# Schatten7.net
KiCad netlist of a schematic drawn in EAGLE
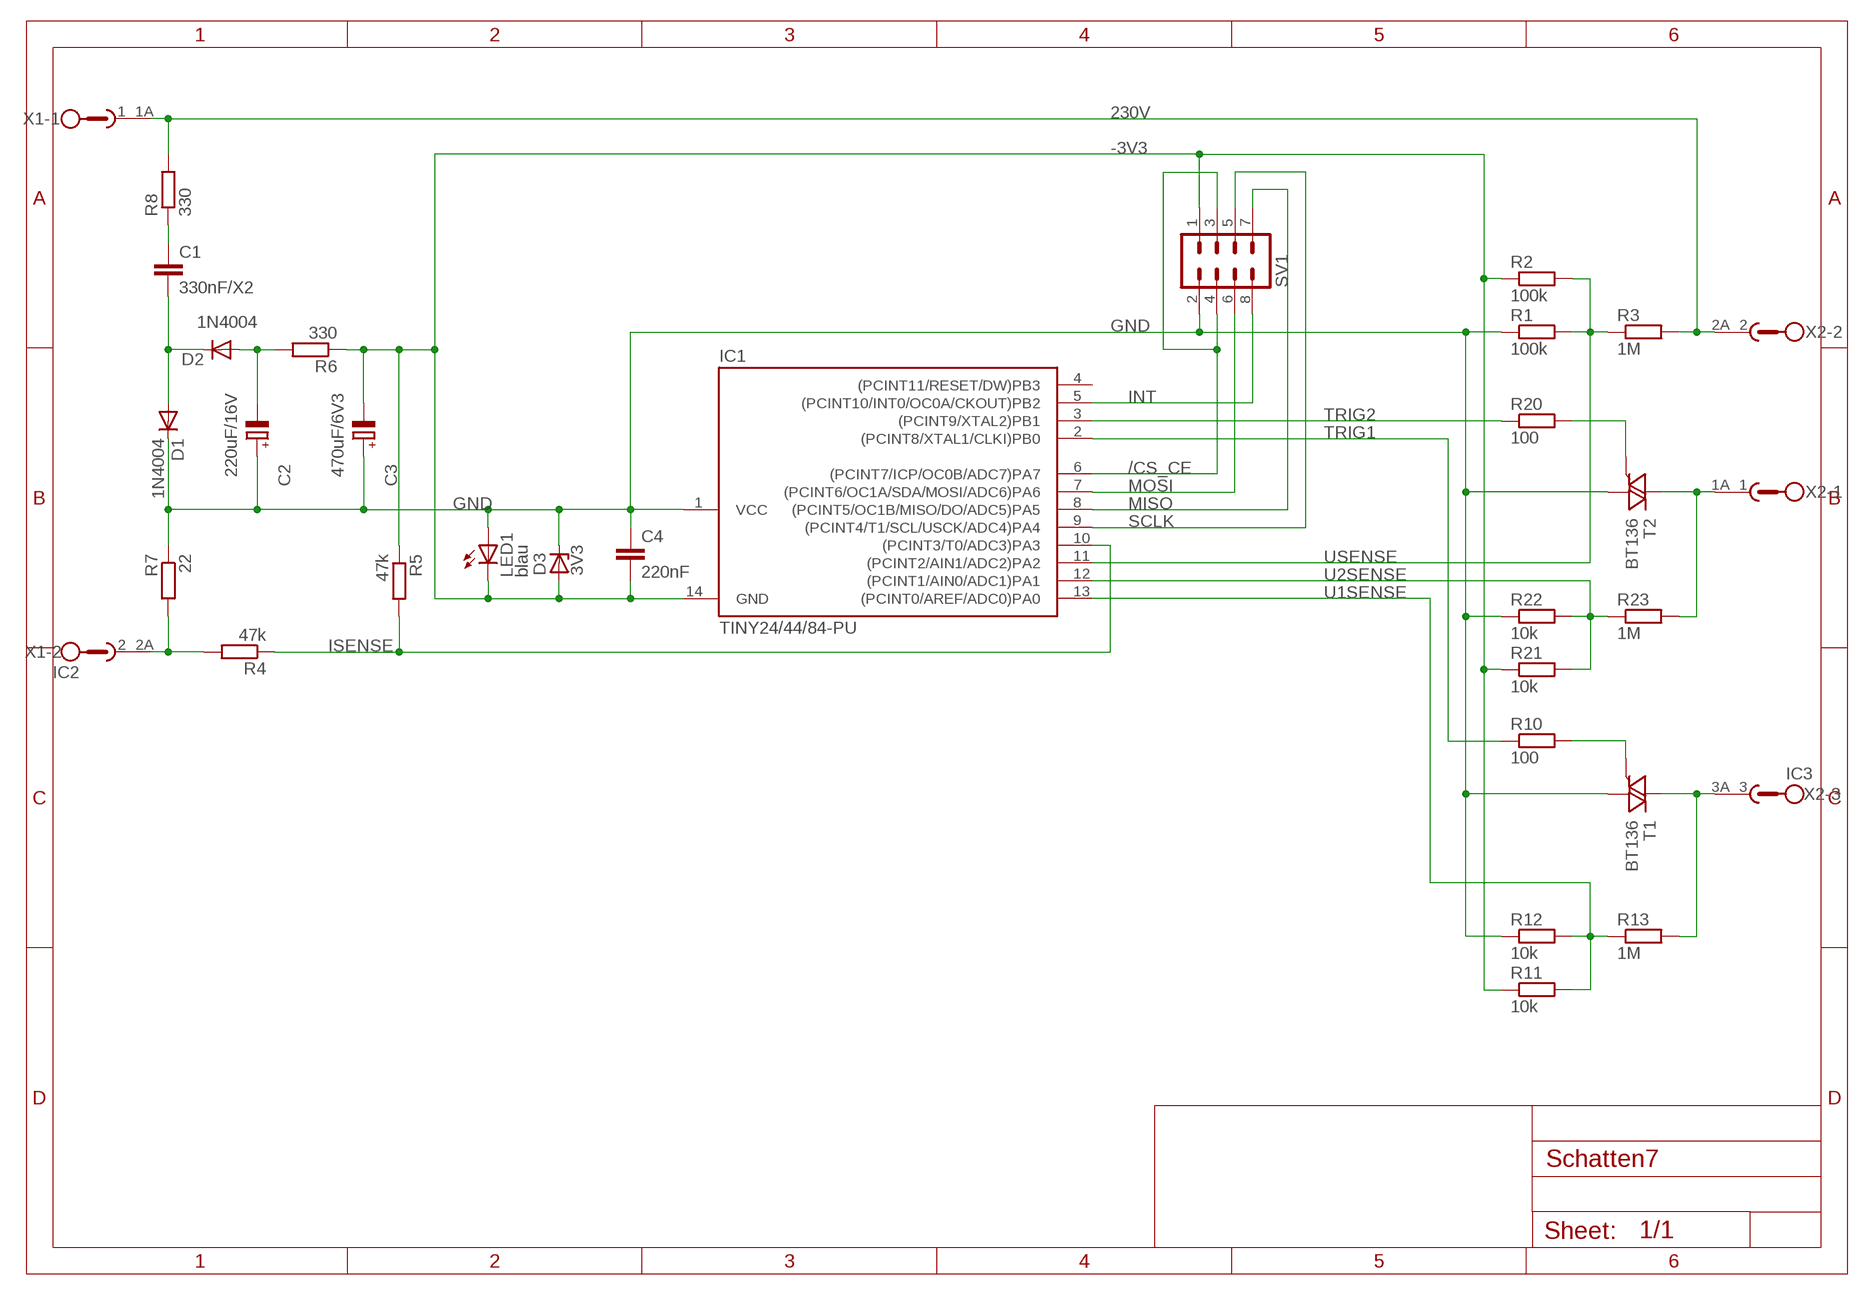
[diagram p0: schematic, sheet 1]

(export (version "E")
  (design (tool "Eeschema 10.0.6"))
  (components
    (comp (ref "C1")
      (value "330nF/X2")
      (footprint "eagle-import:C150-064X183")
      (libsource (lib "eagle-import") (part "C-EU150-064X183"))
    )
    (comp (ref "C2")
      (value "220uF/16V")
      (footprint "eagle-import:E5-8,5")
      (libsource (lib "eagle-import") (part "CPOL-EUE5-8.5"))
    )
    (comp (ref "C3")
      (value "470uF/6V3")
      (footprint "eagle-import:E5-8,5")
      (libsource (lib "eagle-import") (part "CPOL-EUE5-8.5"))
    )
    (comp (ref "C4")
      (value "220nF")
      (footprint "eagle-import:C3225")
      (libsource (lib "eagle-import") (part "C-EUC3225"))
    )
    (comp (ref "D1")
      (value "1N4004")
      (footprint "eagle-import:DO41-10")
      (libsource (lib "eagle-import") (part "1N4004"))
    )
    (comp (ref "D2")
      (value "1N4004")
      (footprint "eagle-import:DO41-10")
      (libsource (lib "eagle-import") (part "1N4004"))
    )
    (comp (ref "D3")
      (value "3V3")
      (footprint "eagle-import:ZDIO-7.5")
      (libsource (lib "eagle-import") (part "ZENER-DIODEZD-7.5"))
    )
    (comp (ref "IC1")
      (value "TINY24/44/84-PU")
      (footprint "eagle-import:DIL14")
      (libsource (lib "eagle-import") (part "TINY24/44/84-PU"))
    )
    (comp (ref "LED1")
      (value "blau")
      (footprint "eagle-import:LED3MM")
      (libsource (lib "eagle-import") (part "LED3MM"))
    )
    (comp (ref "R1")
      (value "100k")
      (footprint "eagle-import:0207_10")
      (libsource (lib "eagle-import") (part "R-EU_0207/10"))
    )
    (comp (ref "R2")
      (value "100k")
      (footprint "eagle-import:0207_10")
      (libsource (lib "eagle-import") (part "R-EU_0207/10"))
    )
    (comp (ref "R3")
      (value "1M")
      (footprint "eagle-import:0207_10")
      (libsource (lib "eagle-import") (part "R-EU_0207/10"))
    )
    (comp (ref "R4")
      (value "47k")
      (footprint "eagle-import:0207_10")
      (libsource (lib "eagle-import") (part "R-EU_0207/10"))
    )
    (comp (ref "R5")
      (value "47k")
      (footprint "eagle-import:0204V")
      (libsource (lib "eagle-import") (part "R-EU_0204/2V"))
    )
    (comp (ref "R6")
      (value "330")
      (footprint "eagle-import:0207_10")
      (libsource (lib "eagle-import") (part "R-EU_0207/10"))
    )
    (comp (ref "R7")
      (value "22")
      (footprint "eagle-import:0207_10")
      (libsource (lib "eagle-import") (part "R-EU_0207/10"))
    )
    (comp (ref "R8")
      (value "330")
      (footprint "eagle-import:0207_10")
      (libsource (lib "eagle-import") (part "R-EU_0207/10"))
    )
    (comp (ref "R10")
      (value "100")
      (footprint "eagle-import:0207_10")
      (libsource (lib "eagle-import") (part "R-EU_0207/10"))
    )
    (comp (ref "R11")
      (value "10k")
      (footprint "eagle-import:0204_7")
      (libsource (lib "eagle-import") (part "R-EU_0204/7"))
    )
    (comp (ref "R12")
      (value "10k")
      (footprint "eagle-import:0207_10")
      (libsource (lib "eagle-import") (part "R-EU_0207/10"))
    )
    (comp (ref "R13")
      (value "1M")
      (footprint "eagle-import:0207_10")
      (libsource (lib "eagle-import") (part "R-EU_0207/10"))
    )
    (comp (ref "R20")
      (value "100")
      (footprint "eagle-import:0207_10")
      (libsource (lib "eagle-import") (part "R-EU_0207/10"))
    )
    (comp (ref "R21")
      (value "10k")
      (footprint "eagle-import:0207_10")
      (libsource (lib "eagle-import") (part "R-EU_0207/10"))
    )
    (comp (ref "R22")
      (value "10k")
      (footprint "eagle-import:0207_10")
      (libsource (lib "eagle-import") (part "R-EU_0207/10"))
    )
    (comp (ref "R23")
      (value "1M")
      (footprint "eagle-import:0207_10")
      (libsource (lib "eagle-import") (part "R-EU_0207/10"))
    )
    (comp (ref "SV1")
      (value "MA04-2")
      (footprint "eagle-import:MA04-2")
      (libsource (lib "eagle-import") (part "MA04-2"))
    )
    (comp (ref "T1")
      (value "BT136")
      (footprint "eagle-import:TO220AB")
      (libsource (lib "eagle-import") (part "BT136"))
    )
    (comp (ref "T2")
      (value "BT136")
      (footprint "eagle-import:TO220AB")
      (libsource (lib "eagle-import") (part "BT136"))
    )
    (comp (ref "X1")
      (value "IC2")
      (footprint "eagle-import:IC2")
      (libsource (lib "eagle-import") (part "IC2"))
    )
    (comp (ref "X2")
      (value "IC3")
      (footprint "eagle-import:IC3")
      (libsource (lib "eagle-import") (part "IC3"))
    )
  )
  (nets
    (net (code "1") (name "/-3V3") (class "Default")
      (node (ref "C3") (pin "-") (pinfunction "-_-") (pintype "passive"))
      (node (ref "C4") (pin "2") (pinfunction "2_2") (pintype "passive"))
      (node (ref "D3") (pin "A") (pinfunction "A_A") (pintype "passive"))
      (node (ref "IC1") (pin "14") (pinfunction "GND_14") (pintype "power_in"))
      (node (ref "LED1") (pin "K") (pinfunction "C_K") (pintype "passive"))
      (node (ref "R11") (pin "1") (pinfunction "1_1") (pintype "passive"))
      (node (ref "R2") (pin "1") (pinfunction "1_1") (pintype "passive"))
      (node (ref "R21") (pin "1") (pinfunction "1_1") (pintype "passive"))
      (node (ref "R5") (pin "1") (pinfunction "1_1") (pintype "passive"))
      (node (ref "R6") (pin "1") (pinfunction "1_1") (pintype "passive"))
      (node (ref "SV1") (pin "1") (pinfunction "1_1") (pintype "passive"))
    )
    (net (code "2") (name "/230V") (class "Default")
      (node (ref "R3") (pin "2") (pinfunction "2_2") (pintype "passive"))
      (node (ref "R8") (pin "2") (pinfunction "2_2") (pintype "passive"))
      (node (ref "X1") (pin "1A") (pinfunction "2_1A") (pintype "passive"))
      (node (ref "X2") (pin "2A") (pinfunction "2_2A") (pintype "passive"))
    )
    (net (code "3") (name "/GND") (class "Default")
      (node (ref "C2") (pin "+") (pinfunction "+_+") (pintype "passive"))
      (node (ref "C3") (pin "+") (pinfunction "+_+") (pintype "passive"))
      (node (ref "C4") (pin "1") (pinfunction "1_1") (pintype "passive"))
      (node (ref "D1") (pin "C") (pinfunction "C_C") (pintype "passive"))
      (node (ref "D3") (pin "C") (pinfunction "C_C") (pintype "passive"))
      (node (ref "IC1") (pin "1") (pinfunction "VCC_1") (pintype "power_in"))
      (node (ref "LED1") (pin "A") (pinfunction "A_A") (pintype "passive"))
      (node (ref "R1") (pin "1") (pinfunction "1_1") (pintype "passive"))
      (node (ref "R12") (pin "1") (pinfunction "1_1") (pintype "passive"))
      (node (ref "R22") (pin "1") (pinfunction "1_1") (pintype "passive"))
      (node (ref "R7") (pin "1") (pinfunction "1_1") (pintype "passive"))
      (node (ref "SV1") (pin "2") (pinfunction "2_2") (pintype "passive"))
      (node (ref "T1") (pin "1") (pinfunction "A1_1") (pintype "passive"))
      (node (ref "T2") (pin "1") (pinfunction "A1_1") (pintype "passive"))
    )
    (net (code "4") (name "/INT") (class "Default")
      (node (ref "IC1") (pin "5") (pinfunction "(PCINT10/INT0/OC0A/CKOUT)PB2_5") (pintype "bidirectional"))
      (node (ref "SV1") (pin "8") (pinfunction "8_8") (pintype "passive"))
    )
    (net (code "5") (name "/ISENSE") (class "Default")
      (node (ref "IC1") (pin "10") (pinfunction "(PCINT3/T0/ADC3)PA3_10") (pintype "bidirectional"))
      (node (ref "R4") (pin "1") (pinfunction "1_1") (pintype "passive"))
      (node (ref "R5") (pin "2") (pinfunction "2_2") (pintype "passive"))
    )
    (net (code "6") (name "/MISO") (class "Default")
      (node (ref "IC1") (pin "8") (pinfunction "(PCINT5/OC1B/MISO/DO/ADC5)PA5_8") (pintype "bidirectional"))
      (node (ref "SV1") (pin "7") (pinfunction "7_7") (pintype "passive"))
    )
    (net (code "7") (name "/MOSI") (class "Default")
      (node (ref "IC1") (pin "7") (pinfunction "(PCINT6/OC1A/SDA/MOSI/ADC6)PA6_7") (pintype "bidirectional"))
      (node (ref "SV1") (pin "6") (pinfunction "6_6") (pintype "passive"))
    )
    (net (code "8") (name "/SCLK") (class "Default")
      (node (ref "IC1") (pin "9") (pinfunction "(PCINT4/T1/SCL/USCK/ADC4)PA4_9") (pintype "bidirectional"))
      (node (ref "SV1") (pin "5") (pinfunction "5_5") (pintype "passive"))
    )
    (net (code "9") (name "/TRIG1") (class "Default")
      (node (ref "IC1") (pin "2") (pinfunction "(PCINT8/XTAL1/CLKI)PB0_2") (pintype "bidirectional"))
      (node (ref "R10") (pin "1") (pinfunction "1_1") (pintype "passive"))
    )
    (net (code "10") (name "/TRIG2") (class "Default")
      (node (ref "IC1") (pin "3") (pinfunction "(PCINT9/XTAL2)PB1_3") (pintype "bidirectional"))
      (node (ref "R20") (pin "1") (pinfunction "1_1") (pintype "passive"))
    )
    (net (code "11") (name "/U1SENSE") (class "Default")
      (node (ref "IC1") (pin "13") (pinfunction "(PCINT0/AREF/ADC0)PA0_13") (pintype "bidirectional"))
      (node (ref "R11") (pin "2") (pinfunction "2_2") (pintype "passive"))
      (node (ref "R12") (pin "2") (pinfunction "2_2") (pintype "passive"))
      (node (ref "R13") (pin "1") (pinfunction "1_1") (pintype "passive"))
    )
    (net (code "12") (name "/U2SENSE") (class "Default")
      (node (ref "IC1") (pin "12") (pinfunction "(PCINT1/AIN0/ADC1)PA1_12") (pintype "bidirectional"))
      (node (ref "R21") (pin "2") (pinfunction "2_2") (pintype "passive"))
      (node (ref "R22") (pin "2") (pinfunction "2_2") (pintype "passive"))
      (node (ref "R23") (pin "1") (pinfunction "1_1") (pintype "passive"))
    )
    (net (code "13") (name "/USENSE") (class "Default")
      (node (ref "IC1") (pin "11") (pinfunction "(PCINT2/AIN1/ADC2)PA2_11") (pintype "bidirectional"))
      (node (ref "R1") (pin "2") (pinfunction "2_2") (pintype "passive"))
      (node (ref "R2") (pin "2") (pinfunction "2_2") (pintype "passive"))
      (node (ref "R3") (pin "1") (pinfunction "1_1") (pintype "passive"))
    )
    (net (code "14") (name "/{slash}CS_CE") (class "Default")
      (node (ref "IC1") (pin "6") (pinfunction "(PCINT7/ICP/OC0B/ADC7)PA7_6") (pintype "bidirectional"))
      (node (ref "SV1") (pin "3") (pinfunction "3_3") (pintype "passive"))
      (node (ref "SV1") (pin "4") (pinfunction "4_4") (pintype "passive"))
    )
    (net (code "15") (name "Net-(C1-Pad1)") (class "Default")
      (node (ref "C1") (pin "1") (pinfunction "1_1") (pintype "passive"))
      (node (ref "R8") (pin "1") (pinfunction "1_1") (pintype "passive"))
    )
    (net (code "16") (name "Net-(C1-Pad2)") (class "Default")
      (node (ref "C1") (pin "2") (pinfunction "2_2") (pintype "passive"))
      (node (ref "D1") (pin "A") (pinfunction "A_A") (pintype "passive"))
      (node (ref "D2") (pin "C") (pinfunction "C_C") (pintype "passive"))
    )
    (net (code "17") (name "Net-(C2-Pad-)") (class "Default")
      (node (ref "C2") (pin "-") (pinfunction "-_-") (pintype "passive"))
      (node (ref "D2") (pin "A") (pinfunction "A_A") (pintype "passive"))
      (node (ref "R6") (pin "2") (pinfunction "2_2") (pintype "passive"))
    )
    (net (code "18") (name "Net-(T1-A2)") (class "Default")
      (node (ref "R13") (pin "2") (pinfunction "2_2") (pintype "passive"))
      (node (ref "T1") (pin "2") (pinfunction "A2_2") (pintype "passive"))
      (node (ref "X2") (pin "3A") (pinfunction "2_3A") (pintype "passive"))
    )
    (net (code "19") (name "Net-(T1-G)") (class "Default")
      (node (ref "R10") (pin "2") (pinfunction "2_2") (pintype "passive"))
      (node (ref "T1") (pin "3") (pinfunction "G_3") (pintype "passive"))
    )
    (net (code "20") (name "Net-(T2-A2)") (class "Default")
      (node (ref "R23") (pin "2") (pinfunction "2_2") (pintype "passive"))
      (node (ref "T2") (pin "2") (pinfunction "A2_2") (pintype "passive"))
      (node (ref "X2") (pin "1A") (pinfunction "2_1A") (pintype "passive"))
    )
    (net (code "21") (name "Net-(T2-G)") (class "Default")
      (node (ref "R20") (pin "2") (pinfunction "2_2") (pintype "passive"))
      (node (ref "T2") (pin "3") (pinfunction "G_3") (pintype "passive"))
    )
    (net (code "22") (name "Net-(X1B-2)") (class "Default")
      (node (ref "R4") (pin "2") (pinfunction "2_2") (pintype "passive"))
      (node (ref "R7") (pin "2") (pinfunction "2_2") (pintype "passive"))
      (node (ref "X1") (pin "2A") (pinfunction "2_2A") (pintype "passive"))
    )
    (net (code "23") (name "unconnected-(IC1-(PCINT11{slash}RESET{slash}DW)PB3-Pad4)") (class "Default")
      (node (ref "IC1") (pin "4") (pinfunction "(PCINT11/RESET/DW)PB3_4") (pintype "bidirectional"))
    )
    (net (code "24") (name "unconnected-(X1-Pad1)") (class "Default")
      (node (ref "X1") (pin "1") (pinfunction "1_1") (pintype "passive"))
    )
    (net (code "25") (name "unconnected-(X1B-1-Pad2)") (class "Default")
      (node (ref "X1") (pin "2") (pinfunction "1_2") (pintype "passive"))
    )
    (net (code "26") (name "unconnected-(X2-Pad1)") (class "Default")
      (node (ref "X2") (pin "1") (pinfunction "1_1") (pintype "passive"))
    )
    (net (code "27") (name "unconnected-(X2B-1-Pad2)") (class "Default")
      (node (ref "X2") (pin "2") (pinfunction "1_2") (pintype "passive"))
    )
    (net (code "28") (name "unconnected-(X2C-1-Pad3)") (class "Default")
      (node (ref "X2") (pin "3") (pinfunction "1_3") (pintype "passive"))
    )
  )
)
